# tkp-v1.net
KiCad netlist of a schematic drawn in EAGLE
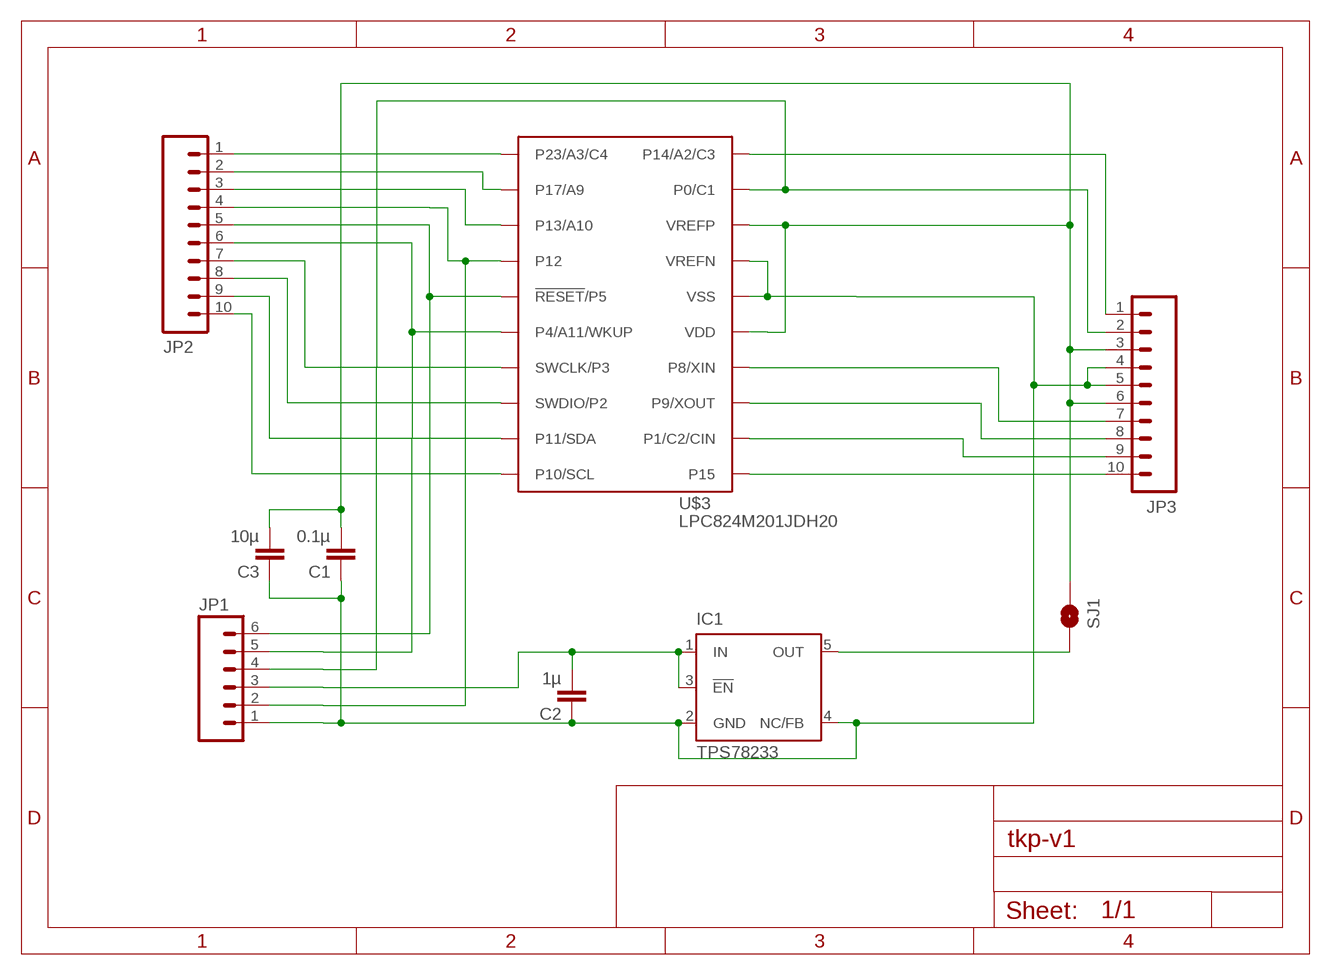
[diagram p0: schematic, sheet 1]

(export (version "E")
  (design (tool "Eeschema 10.0.6"))
  (components
    (comp (ref "C1")
      (value "0.1µ")
      (footprint "eagle-import:C0603K")
      (libsource (lib "eagle-import") (part "C-EUC0603K"))
    )
    (comp (ref "C2")
      (value "1µ")
      (footprint "eagle-import:C0603K")
      (libsource (lib "eagle-import") (part "C-EUC0603K"))
    )
    (comp (ref "C3")
      (value "10µ")
      (footprint "eagle-import:C0805K")
      (libsource (lib "eagle-import") (part "C-EUC0805K"))
    )
    (comp (ref "IC1")
      (value "TPS78233")
      (footprint "eagle-import:SOT23-DBV")
      (fields (field (name "MF") "TEXAS INSTRUMENTS") (field (name "MPN") "TPS77001DBVT"))
      (libsource (lib "eagle-import") (part "TPS77001"))
    )
    (comp (ref "JP1")
      (value "M06LONGPADS")
      (footprint "eagle-import:1X06_LONGPADS")
      (libsource (lib "eagle-import") (part "M06LONGPADS"))
    )
    (comp (ref "JP2")
      (value "M10NO_SILK_PTH_FEMALE")
      (footprint "eagle-import:1X10_NO_SILK")
      (libsource (lib "eagle-import") (part "M10NO_SILK_PTH_FEMALE"))
    )
    (comp (ref "JP3")
      (value "M10NO_SILK_PTH_FEMALE")
      (footprint "eagle-import:1X10_NO_SILK")
      (libsource (lib "eagle-import") (part "M10NO_SILK_PTH_FEMALE"))
    )
    (comp (ref "SJ1")
      (value "SOLDERJUMPERTRACE")
      (footprint "eagle-import:SJ_2S-TRACE")
      (libsource (lib "eagle-import") (part "SOLDERJUMPERTRACE"))
    )
    (comp (ref "U$3")
      (value "LPC824M201JDH20")
      (footprint "eagle-import:TSSOP20")
      (libsource (lib "eagle-import") (part "LPC824M201JDH20"))
    )
  )
  (nets
    (net (code "1") (name "Net-(IC1-GND)") (class "Default")
      (node (ref "C1") (pin "1") (pinfunction "1_1") (pintype "passive"))
      (node (ref "C2") (pin "1") (pinfunction "1_1") (pintype "passive"))
      (node (ref "C3") (pin "1") (pinfunction "1_1") (pintype "passive"))
      (node (ref "IC1") (pin "2") (pinfunction "GND_2") (pintype "power_in"))
      (node (ref "IC1") (pin "4") (pinfunction "NC/FB_4") (pintype "passive"))
      (node (ref "JP1") (pin "1") (pinfunction "1_1") (pintype "passive"))
      (node (ref "JP3") (pin "4") (pinfunction "4_4") (pintype "passive"))
      (node (ref "JP3") (pin "5") (pinfunction "5_5") (pintype "passive"))
      (node (ref "U$3") (pin "16") (pinfunction "VSS_16") (pintype "bidirectional"))
      (node (ref "U$3") (pin "17") (pinfunction "VREFN_17") (pintype "bidirectional"))
    )
    (net (code "2") (name "Net-(IC1-IN)") (class "Default")
      (node (ref "C2") (pin "2") (pinfunction "2_2") (pintype "passive"))
      (node (ref "IC1") (pin "1") (pinfunction "IN_1") (pintype "input"))
      (node (ref "IC1") (pin "3") (pinfunction "~{EN}_3") (pintype "input"))
      (node (ref "JP1") (pin "3") (pinfunction "3_3") (pintype "passive"))
    )
    (net (code "3") (name "Net-(IC1-OUT)") (class "Default")
      (node (ref "IC1") (pin "5") (pinfunction "OUT_5") (pintype "passive"))
      (node (ref "SJ1") (pin "2") (pinfunction "2_2") (pintype "passive"))
    )
    (net (code "4") (name "Net-(U$3-P0{slash}C1)") (class "Default")
      (node (ref "JP1") (pin "4") (pinfunction "4_4") (pintype "passive"))
      (node (ref "JP3") (pin "2") (pinfunction "2_2") (pintype "passive"))
      (node (ref "U$3") (pin "19") (pinfunction "P0/C1_19") (pintype "bidirectional"))
    )
    (net (code "5") (name "Net-(U$3-P1{slash}C2{slash}CIN)") (class "Default")
      (node (ref "JP3") (pin "9") (pinfunction "9_9") (pintype "passive"))
      (node (ref "U$3") (pin "12") (pinfunction "P1/C2/CIN_12") (pintype "bidirectional"))
    )
    (net (code "6") (name "Net-(U$3-P4{slash}A11{slash}WKUP)") (class "Default")
      (node (ref "JP1") (pin "5") (pinfunction "5_5") (pintype "passive"))
      (node (ref "JP2") (pin "6") (pinfunction "6_6") (pintype "passive"))
      (node (ref "U$3") (pin "6") (pinfunction "P4/A11/WKUP_6") (pintype "bidirectional"))
    )
    (net (code "7") (name "Net-(U$3-P8{slash}XIN)") (class "Default")
      (node (ref "JP3") (pin "7") (pinfunction "7_7") (pintype "passive"))
      (node (ref "U$3") (pin "14") (pinfunction "P8/XIN_14") (pintype "bidirectional"))
    )
    (net (code "8") (name "Net-(U$3-P9{slash}XOUT)") (class "Default")
      (node (ref "JP3") (pin "8") (pinfunction "8_8") (pintype "passive"))
      (node (ref "U$3") (pin "13") (pinfunction "P9/XOUT_13") (pintype "bidirectional"))
    )
    (net (code "9") (name "Net-(U$3-P10{slash}SCL)") (class "Default")
      (node (ref "JP2") (pin "10") (pinfunction "10_10") (pintype "passive"))
      (node (ref "U$3") (pin "10") (pinfunction "P10/SCL_10") (pintype "bidirectional"))
    )
    (net (code "10") (name "Net-(U$3-P11{slash}SDA)") (class "Default")
      (node (ref "JP2") (pin "9") (pinfunction "9_9") (pintype "passive"))
      (node (ref "U$3") (pin "9") (pinfunction "P11/SDA_9") (pintype "bidirectional"))
    )
    (net (code "11") (name "Net-(U$3-P12)") (class "Default")
      (node (ref "JP1") (pin "2") (pinfunction "2_2") (pintype "passive"))
      (node (ref "JP2") (pin "4") (pinfunction "4_4") (pintype "passive"))
      (node (ref "U$3") (pin "4") (pinfunction "P12_4") (pintype "bidirectional"))
    )
    (net (code "12") (name "Net-(U$3-P13{slash}A10)") (class "Default")
      (node (ref "JP2") (pin "3") (pinfunction "3_3") (pintype "passive"))
      (node (ref "U$3") (pin "3") (pinfunction "P13/A10_3") (pintype "bidirectional"))
    )
    (net (code "13") (name "Net-(U$3-P14{slash}A2{slash}C3)") (class "Default")
      (node (ref "JP3") (pin "1") (pinfunction "1_1") (pintype "passive"))
      (node (ref "U$3") (pin "20") (pinfunction "P14/A2/C3_20") (pintype "bidirectional"))
    )
    (net (code "14") (name "Net-(U$3-P15)") (class "Default")
      (node (ref "JP3") (pin "10") (pinfunction "10_10") (pintype "passive"))
      (node (ref "U$3") (pin "11") (pinfunction "P15_11") (pintype "bidirectional"))
    )
    (net (code "15") (name "Net-(U$3-P17{slash}A9)") (class "Default")
      (node (ref "JP2") (pin "2") (pinfunction "2_2") (pintype "passive"))
      (node (ref "U$3") (pin "2") (pinfunction "P17/A9_2") (pintype "bidirectional"))
    )
    (net (code "16") (name "Net-(U$3-P23{slash}A3{slash}C4)") (class "Default")
      (node (ref "JP2") (pin "1") (pinfunction "1_1") (pintype "passive"))
      (node (ref "U$3") (pin "1") (pinfunction "P23/A3/C4_1") (pintype "bidirectional"))
    )
    (net (code "17") (name "Net-(U$3-SWCLK{slash}P3)") (class "Default")
      (node (ref "JP2") (pin "7") (pinfunction "7_7") (pintype "passive"))
      (node (ref "U$3") (pin "7") (pinfunction "SWCLK/P3_7") (pintype "bidirectional"))
    )
    (net (code "18") (name "Net-(U$3-SWDIO{slash}P2)") (class "Default")
      (node (ref "JP2") (pin "8") (pinfunction "8_8") (pintype "passive"))
      (node (ref "U$3") (pin "8") (pinfunction "SWDIO/P2_8") (pintype "bidirectional"))
    )
    (net (code "19") (name "Net-(U$3-VDD)") (class "Default")
      (node (ref "C1") (pin "2") (pinfunction "2_2") (pintype "passive"))
      (node (ref "C3") (pin "2") (pinfunction "2_2") (pintype "passive"))
      (node (ref "JP3") (pin "3") (pinfunction "3_3") (pintype "passive"))
      (node (ref "JP3") (pin "6") (pinfunction "6_6") (pintype "passive"))
      (node (ref "SJ1") (pin "1") (pinfunction "1_1") (pintype "passive"))
      (node (ref "U$3") (pin "15") (pinfunction "VDD_15") (pintype "bidirectional"))
      (node (ref "U$3") (pin "18") (pinfunction "VREFP_18") (pintype "bidirectional"))
    )
    (net (code "20") (name "Net-(U$3-~{RESET}{slash}P5)") (class "Default")
      (node (ref "JP1") (pin "6") (pinfunction "6_6") (pintype "passive"))
      (node (ref "JP2") (pin "5") (pinfunction "5_5") (pintype "passive"))
      (node (ref "U$3") (pin "5") (pinfunction "~{RESET}/P5_5") (pintype "bidirectional"))
    )
  )
)
